# MIcroSD_Card.net
KiCad netlist of a schematic drawn in Altium Designer
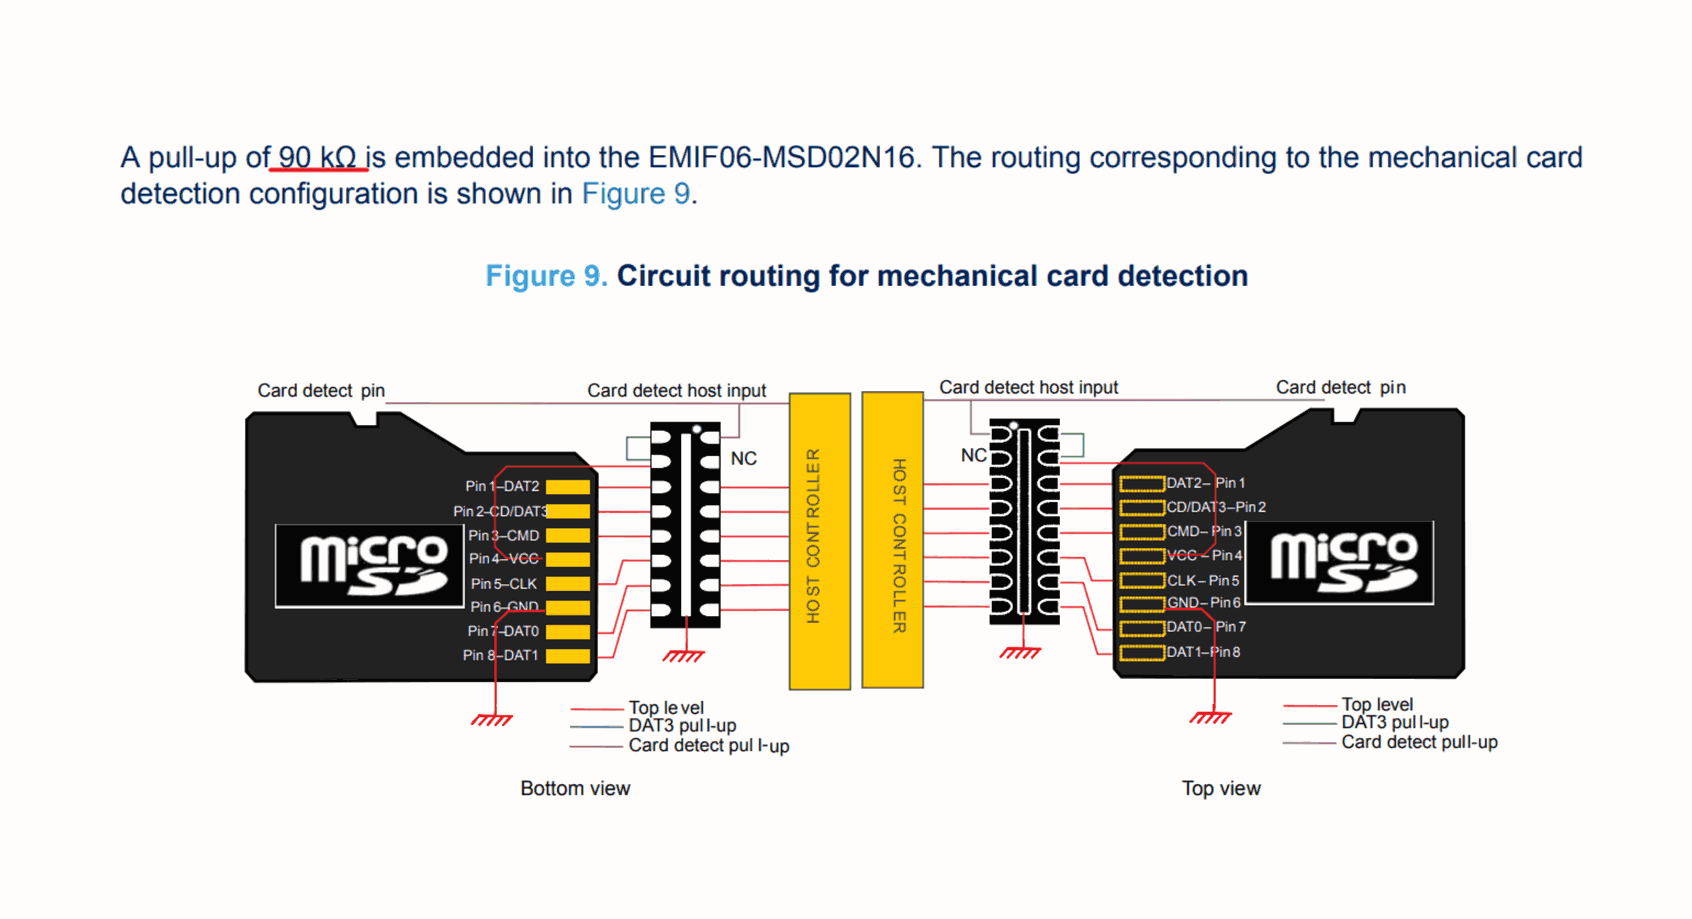
[diagram p0: MIcroSD_Card.SchDoc, top left]
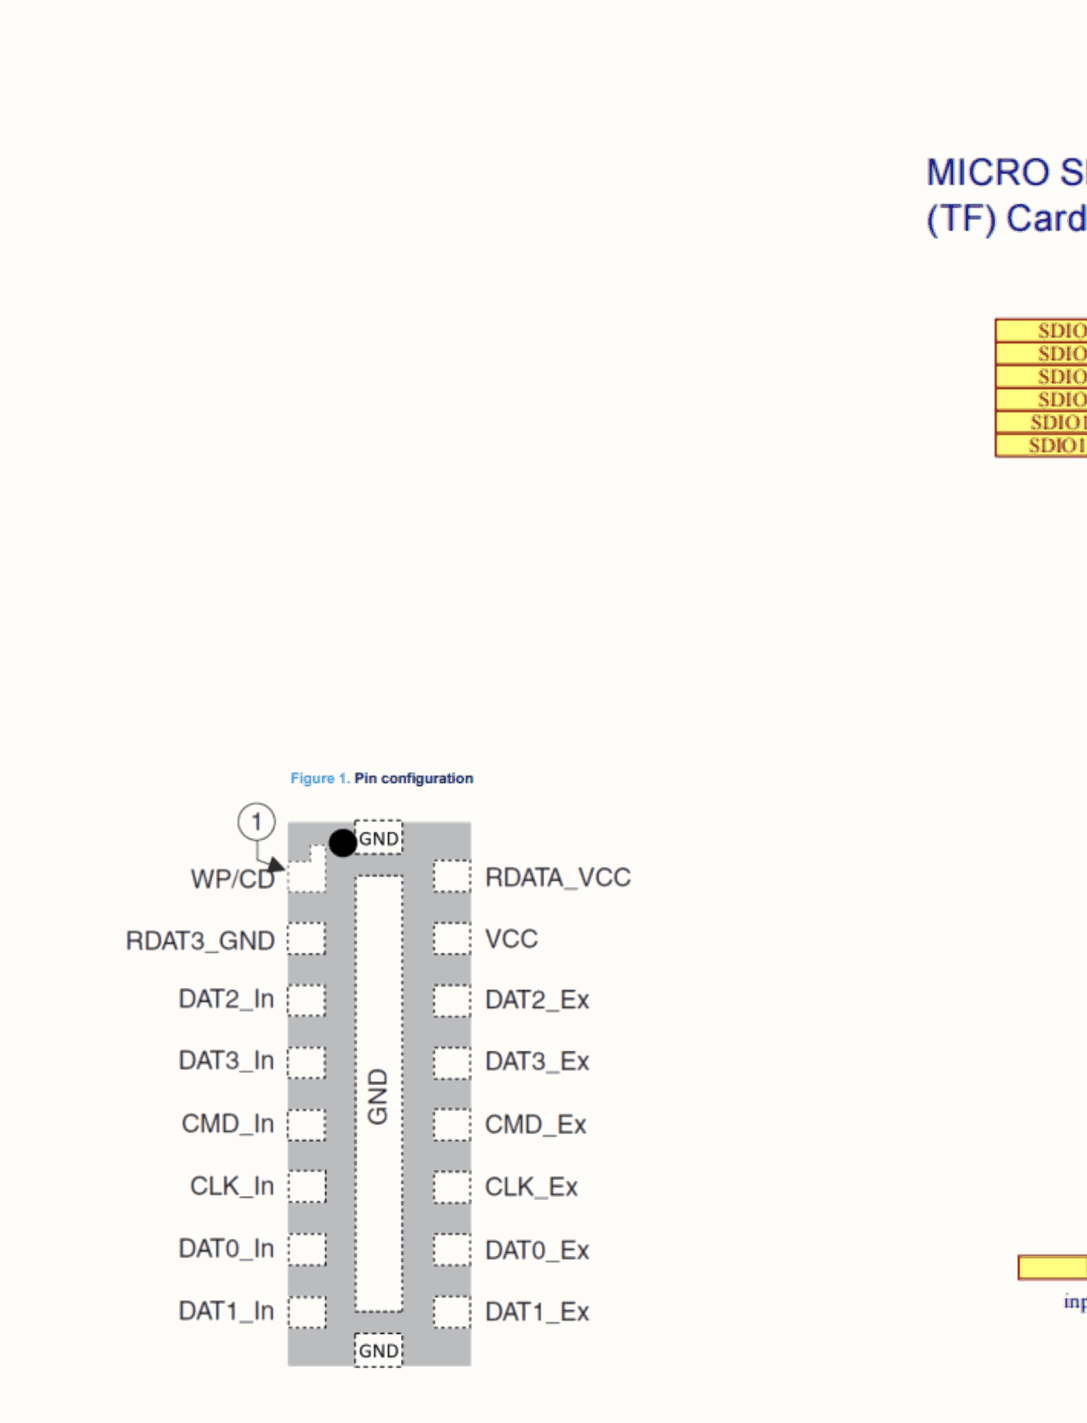
[diagram p1: MIcroSD_Card.SchDoc, top middle]
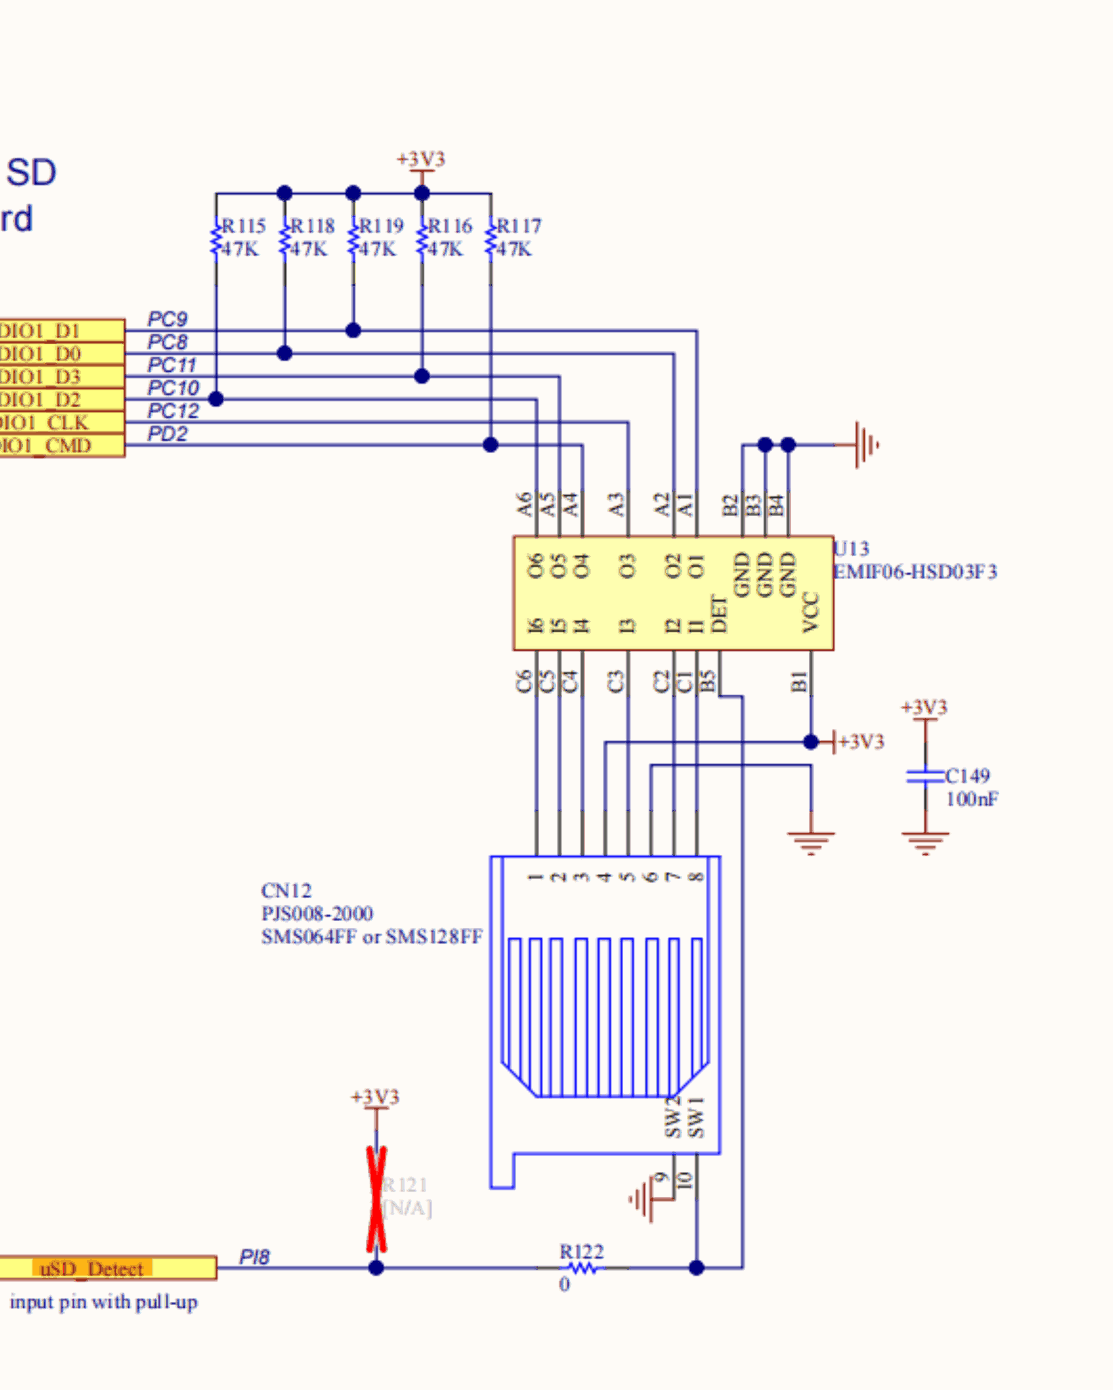
[diagram p2: MIcroSD_Card.SchDoc, top right]
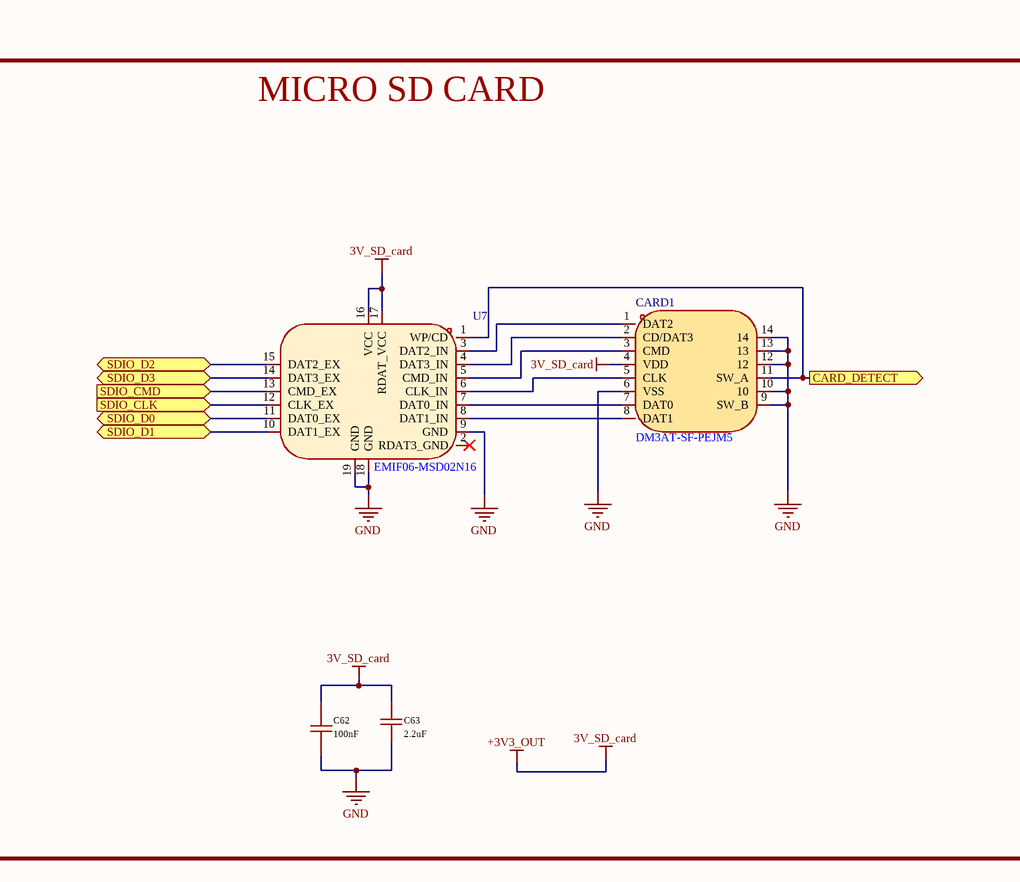
[diagram p3: MIcroSD_Card.SchDoc, bottom left]
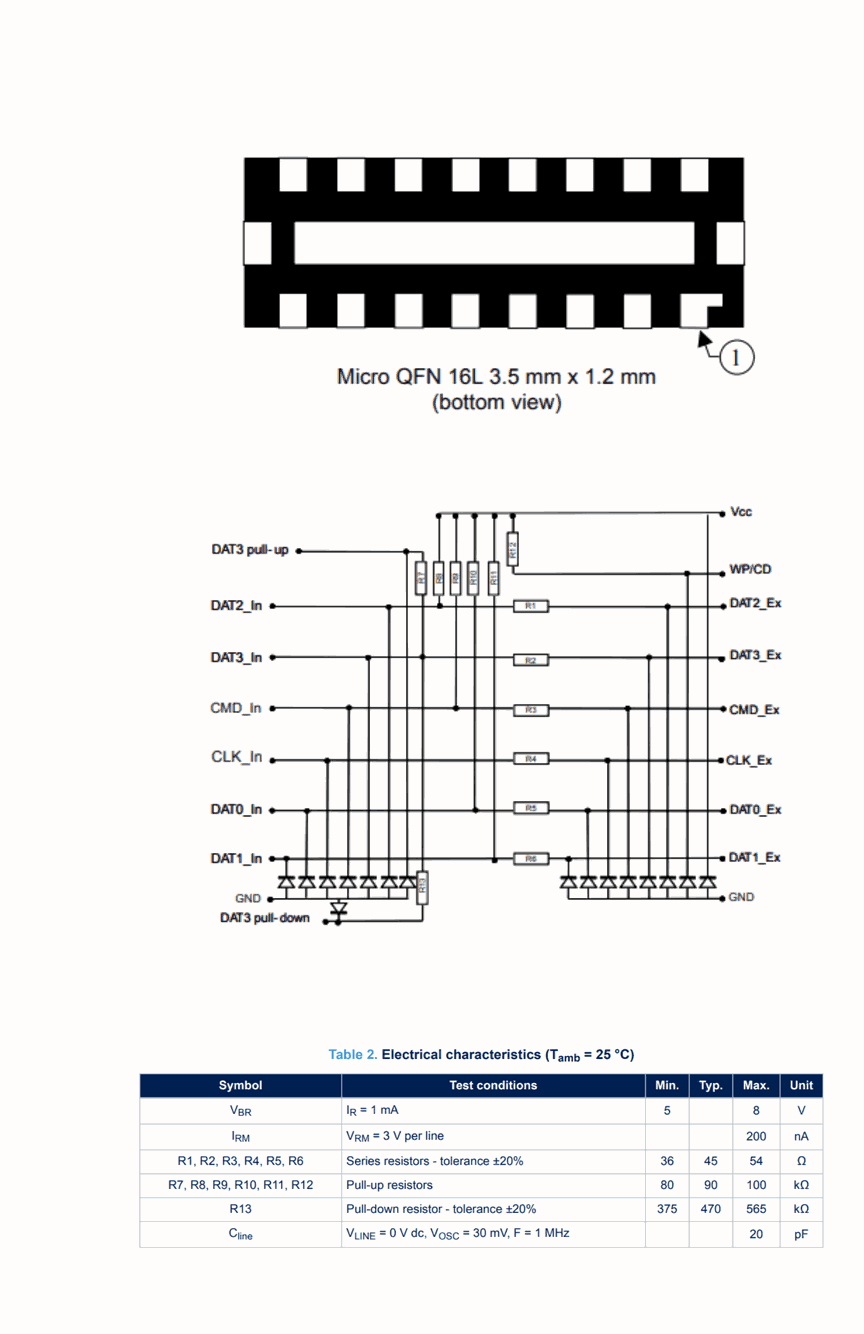
[diagram p4: MIcroSD_Card.SchDoc, bottom middle]
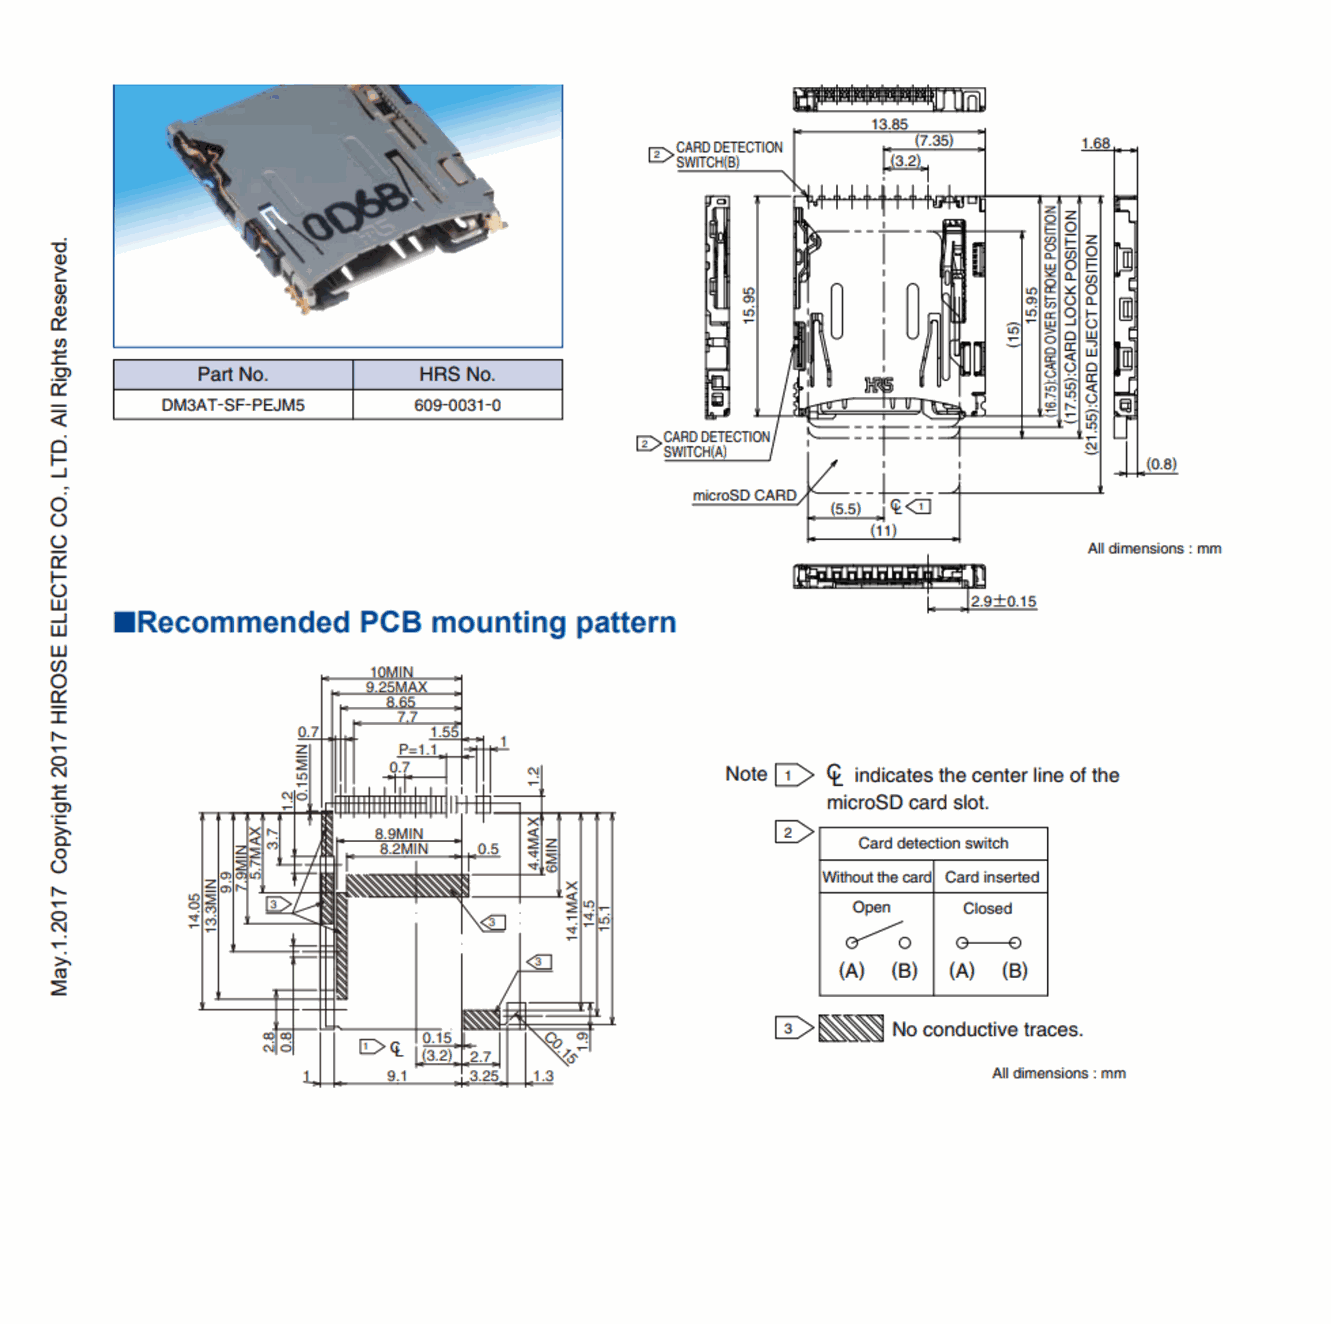
[diagram p5: MIcroSD_Card.SchDoc, bottom right]

(export (version "E")
  (design (tool "Eeschema 10.0.6"))
  (components
    (comp (ref "C62")
      (value "100nF")
      (footprint "C_0603")
      (fields
        (field (name "MANUFACTURER") "YAGEO(国巨)")
        (field (name "MANUFACTURER PART") "CC0603KRX7R9BB104")
        (field (name "TOLERANCE") "±10%")
      )
      (libsource (lib "altium-import") (part "root_3_CC0603KRX7R9BB104_"))
    )
    (comp (ref "C63")
      (value "2.2uF")
      (footprint "C_0805")
      (fields
        (field (name "MANUFACTURER") "SAMSUNG(三星)")
        (field (name "MANUFACTURER PART") "CL21B225KAFNNNE")
        (field (name "TOLERANCE") "±10%")
      )
      (libsource (lib "altium-import") (part "root_1_CL21B225KAFNNNE_"))
    )
    (comp (ref "CARD1")
      (value "DM3AT-SF-PEJM5")
      (footprint "SD-SMD_DM3AT-SF-PEJM5")
      (fields (field (name "MANUFACTURER") "HRS(广濑)"))
      (libsource (lib "EsoCore_Edge_Board_V1-0.0.0") (part "DM3AT-SF-PEJM5"))
    )
    (comp (ref "U7")
      (value "EMIF06-MSD02N16")
      (footprint "QFN-16L_L3.5-W1.2-P0.40_EMIF06-MSD02N16")
      (fields (field (name "MANUFACTURER") "ST(意法半导体)"))
      (libsource (lib "EsoCore_Edge_Board_V1-0.0.0") (part "EMIF06-MSD02N16"))
    )
  )
  (nets
    (net (code "1") (name "+3V3_OUT") (class "Default")
      (node (ref "C62") (pin "1") (pinfunction "1_1") (pintype "passive"))
      (node (ref "C63") (pin "2") (pinfunction "2_2") (pintype "passive"))
      (node (ref "CARD1") (pin "4") (pinfunction "VDD_4") (pintype "passive"))
      (node (ref "U7") (pin "16") (pinfunction "VCC_16") (pintype "passive"))
      (node (ref "U7") (pin "17") (pinfunction "RDAT_VCC_17") (pintype "passive"))
    )
    (net (code "2") (name "/CARD_DETECT") (class "Default")
      (node (ref "CARD1") (pin "11") (pinfunction "SW_A_11") (pintype "passive"))
      (node (ref "U7") (pin "1") (pinfunction "WP/CD_1") (pintype "passive"))
    )
    (net (code "3") (name "/SDIO_CLK") (class "Default")
      (node (ref "U7") (pin "12") (pinfunction "CLK_EX_12") (pintype "passive"))
    )
    (net (code "4") (name "/SDIO_CMD") (class "Default")
      (node (ref "U7") (pin "13") (pinfunction "CMD_EX_13") (pintype "passive"))
    )
    (net (code "5") (name "/SDIO_D0") (class "Default")
      (node (ref "U7") (pin "11") (pinfunction "DAT0_EX_11") (pintype "passive"))
    )
    (net (code "6") (name "/SDIO_D1") (class "Default")
      (node (ref "U7") (pin "10") (pinfunction "DAT1_EX_10") (pintype "passive"))
    )
    (net (code "7") (name "/SDIO_D2") (class "Default")
      (node (ref "U7") (pin "15") (pinfunction "DAT2_EX_15") (pintype "passive"))
    )
    (net (code "8") (name "/SDIO_D3") (class "Default")
      (node (ref "U7") (pin "14") (pinfunction "DAT3_EX_14") (pintype "passive"))
    )
    (net (code "9") (name "GND") (class "Default")
      (node (ref "C62") (pin "2") (pinfunction "2_2") (pintype "passive"))
      (node (ref "C63") (pin "1") (pinfunction "1_1") (pintype "passive"))
      (node (ref "CARD1") (pin "10") (pinfunction "10_10") (pintype "passive"))
      (node (ref "CARD1") (pin "12") (pinfunction "12_12") (pintype "passive"))
      (node (ref "CARD1") (pin "13") (pinfunction "13_13") (pintype "passive"))
      (node (ref "CARD1") (pin "14") (pinfunction "14_14") (pintype "passive"))
      (node (ref "CARD1") (pin "6") (pinfunction "VSS_6") (pintype "passive"))
      (node (ref "CARD1") (pin "9") (pinfunction "SW_B_9") (pintype "passive"))
      (node (ref "U7") (pin "18") (pinfunction "GND_18") (pintype "passive"))
      (node (ref "U7") (pin "19") (pinfunction "GND_19") (pintype "passive"))
      (node (ref "U7") (pin "9") (pinfunction "GND_9") (pintype "passive"))
    )
    (net (code "10") (name "Net-(CARD1-CD{slash}DAT3)") (class "Default")
      (node (ref "CARD1") (pin "2") (pinfunction "CD/DAT3_2") (pintype "passive"))
      (node (ref "U7") (pin "4") (pinfunction "DAT3_IN_4") (pintype "passive"))
    )
    (net (code "11") (name "Net-(CARD1-CLK)") (class "Default")
      (node (ref "CARD1") (pin "5") (pinfunction "CLK_5") (pintype "passive"))
      (node (ref "U7") (pin "6") (pinfunction "CLK_IN_6") (pintype "passive"))
    )
    (net (code "12") (name "Net-(CARD1-CMD)") (class "Default")
      (node (ref "CARD1") (pin "3") (pinfunction "CMD_3") (pintype "passive"))
      (node (ref "U7") (pin "5") (pinfunction "CMD_IN_5") (pintype "passive"))
    )
    (net (code "13") (name "Net-(CARD1-DAT0)") (class "Default")
      (node (ref "CARD1") (pin "7") (pinfunction "DAT0_7") (pintype "passive"))
      (node (ref "U7") (pin "7") (pinfunction "DAT0_IN_7") (pintype "passive"))
    )
    (net (code "14") (name "Net-(CARD1-DAT1)") (class "Default")
      (node (ref "CARD1") (pin "8") (pinfunction "DAT1_8") (pintype "passive"))
      (node (ref "U7") (pin "8") (pinfunction "DAT1_IN_8") (pintype "passive"))
    )
    (net (code "15") (name "Net-(CARD1-DAT2)") (class "Default")
      (node (ref "CARD1") (pin "1") (pinfunction "DAT2_1") (pintype "passive"))
      (node (ref "U7") (pin "3") (pinfunction "DAT2_IN_3") (pintype "passive"))
    )
    (net (code "16") (name "unconnected-(U7-RDAT3_GND-Pad2)") (class "Default")
      (node (ref "U7") (pin "2") (pinfunction "RDAT3_GND_2") (pintype "passive+no_connect"))
    )
  )
)
